# IMU_Sensor.net
KiCad netlist of a schematic drawn in Altium Designer
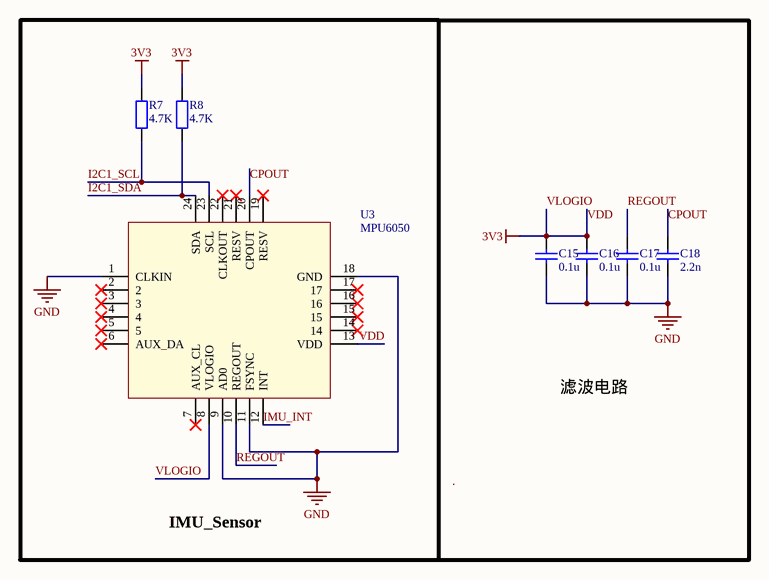
[diagram p0: IMU_Sensor.SchDoc]

(export (version "E")
  (design (tool "Eeschema 10.0.6"))
  (components
    (comp (ref "C15")
      (value "0.1u")
      (footprint "C0402_M")
      (description "贴片电容/MLCC电容")
      (libsource (lib "0.1 - 电阻-电容-电感-保险丝-晶振-晶体-磁珠-电位器-法拉电容-馈通电容") (part "C"))
    )
    (comp (ref "C16")
      (value "0.1u")
      (footprint "C0402_M")
      (description "贴片电容/MLCC电容")
      (libsource (lib "0.1 - 电阻-电容-电感-保险丝-晶振-晶体-磁珠-电位器-法拉电容-馈通电容") (part "C"))
    )
    (comp (ref "C17")
      (value "0.1u")
      (footprint "C0402_M")
      (description "贴片电容/MLCC电容")
      (libsource (lib "0.1 - 电阻-电容-电感-保险丝-晶振-晶体-磁珠-电位器-法拉电容-馈通电容") (part "C"))
    )
    (comp (ref "C18")
      (value "2.2n")
      (footprint "C0402_M")
      (description "贴片电容/MLCC电容")
      (libsource (lib "0.1 - 电阻-电容-电感-保险丝-晶振-晶体-磁珠-电位器-法拉电容-馈通电容") (part "C"))
    )
    (comp (ref "R7")
      (value "4.7K")
      (footprint "R0402_M")
      (description "贴片电阻")
      (libsource (lib "0.1 - 电阻-电容-电感-保险丝-晶振-晶体-磁珠-电位器-法拉电容-馈通电容") (part "R"))
    )
    (comp (ref "R8")
      (value "4.7K")
      (footprint "R0402_M")
      (description "贴片电阻")
      (libsource (lib "0.1 - 电阻-电容-电感-保险丝-晶振-晶体-磁珠-电位器-法拉电容-馈通电容") (part "R"))
    )
    (comp (ref "U3")
      (value "MPU6050")
      (footprint "PCB1:QFN-24_L4.0-W4.0-P0.50-BL-EP2.7")
      (description "三轴加速度+三轴陀螺仪")
      (libsource (lib "0.9 - 传感器-存储器-模块") (part "MPU6050"))
    )
  )
  (nets
    (net (code "1") (name "/CPOUT") (class "Default")
      (node (ref "C18") (pin "2") (pinfunction "2_2") (pintype "passive"))
      (node (ref "U3") (pin "20") (pinfunction "CPOUT_20") (pintype "passive"))
    )
    (net (code "2") (name "/I2C1_SCL") (class "Default")
      (node (ref "R7") (pin "1") (pinfunction "1_1") (pintype "passive"))
      (node (ref "U3") (pin "23") (pinfunction "SCL_23") (pintype "passive"))
    )
    (net (code "3") (name "/I2C1_SDA") (class "Default")
      (node (ref "R8") (pin "1") (pinfunction "1_1") (pintype "passive"))
      (node (ref "U3") (pin "24") (pinfunction "SDA_24") (pintype "passive"))
    )
    (net (code "4") (name "/IMU_INT") (class "Default")
      (node (ref "U3") (pin "12") (pinfunction "INT_12") (pintype "passive"))
    )
    (net (code "5") (name "/REGOUT") (class "Default")
      (node (ref "C17") (pin "2") (pinfunction "2_2") (pintype "passive"))
      (node (ref "U3") (pin "10") (pinfunction "REGOUT_10") (pintype "passive"))
    )
    (net (code "7") (name "3V3") (class "Default")
      (node (ref "C15") (pin "2") (pinfunction "2_2") (pintype "passive"))
      (node (ref "C16") (pin "2") (pinfunction "2_2") (pintype "passive"))
      (node (ref "R7") (pin "2") (pinfunction "2_2") (pintype "passive"))
      (node (ref "R8") (pin "2") (pinfunction "2_2") (pintype "passive"))
      (node (ref "U3") (pin "13") (pinfunction "VDD_13") (pintype "passive"))
      (node (ref "U3") (pin "8") (pinfunction "VLOGIO_8") (pintype "passive"))
    )
    (net (code "8") (name "GND") (class "Default")
      (node (ref "C15") (pin "1") (pinfunction "1_1") (pintype "passive"))
      (node (ref "C16") (pin "1") (pinfunction "1_1") (pintype "passive"))
      (node (ref "C17") (pin "1") (pinfunction "1_1") (pintype "passive"))
      (node (ref "C18") (pin "1") (pinfunction "1_1") (pintype "passive"))
      (node (ref "U3") (pin "1") (pinfunction "CLKIN_1") (pintype "passive"))
      (node (ref "U3") (pin "11") (pinfunction "FSYNC_11") (pintype "passive"))
      (node (ref "U3") (pin "18") (pinfunction "GND_18") (pintype "passive"))
      (node (ref "U3") (pin "9") (pinfunction "AD0_9") (pintype "passive"))
    )
    (net (code "9") (name "unconnected-(U3-AUX_CL-Pad7)") (class "Default")
      (node (ref "U3") (pin "7") (pinfunction "AUX_CL_7") (pintype "passive+no_connect"))
    )
    (net (code "10") (name "unconnected-(U3-AUX_DA-Pad6)") (class "Default")
      (node (ref "U3") (pin "6") (pinfunction "AUX_DA_6") (pintype "passive+no_connect"))
    )
    (net (code "11") (name "unconnected-(U3-CLKOUT-Pad22)") (class "Default")
      (node (ref "U3") (pin "22") (pinfunction "CLKOUT_22") (pintype "passive+no_connect"))
    )
    (net (code "12") (name "unconnected-(U3-Pad2)") (class "Default")
      (node (ref "U3") (pin "2") (pinfunction "2_2") (pintype "passive+no_connect"))
    )
    (net (code "13") (name "unconnected-(U3-Pad3)") (class "Default")
      (node (ref "U3") (pin "3") (pinfunction "3_3") (pintype "passive+no_connect"))
    )
    (net (code "14") (name "unconnected-(U3-Pad4)") (class "Default")
      (node (ref "U3") (pin "4") (pinfunction "4_4") (pintype "passive+no_connect"))
    )
    (net (code "15") (name "unconnected-(U3-Pad5)") (class "Default")
      (node (ref "U3") (pin "5") (pinfunction "5_5") (pintype "passive+no_connect"))
    )
    (net (code "16") (name "unconnected-(U3-Pad14)") (class "Default")
      (node (ref "U3") (pin "14") (pinfunction "14_14") (pintype "passive+no_connect"))
    )
    (net (code "17") (name "unconnected-(U3-Pad15)") (class "Default")
      (node (ref "U3") (pin "15") (pinfunction "15_15") (pintype "passive+no_connect"))
    )
    (net (code "18") (name "unconnected-(U3-Pad16)") (class "Default")
      (node (ref "U3") (pin "16") (pinfunction "16_16") (pintype "passive+no_connect"))
    )
    (net (code "19") (name "unconnected-(U3-Pad17)") (class "Default")
      (node (ref "U3") (pin "17") (pinfunction "17_17") (pintype "passive+no_connect"))
    )
    (net (code "20") (name "unconnected-(U3-RESV-Pad19)") (class "Default")
      (node (ref "U3") (pin "19") (pinfunction "RESV_19") (pintype "passive+no_connect"))
    )
    (net (code "21") (name "unconnected-(U3-RESV-Pad21)") (class "Default")
      (node (ref "U3") (pin "21") (pinfunction "RESV_21") (pintype "passive+no_connect"))
    )
  )
)
